# Memory.net
KiCad netlist of a schematic drawn in Altium Designer
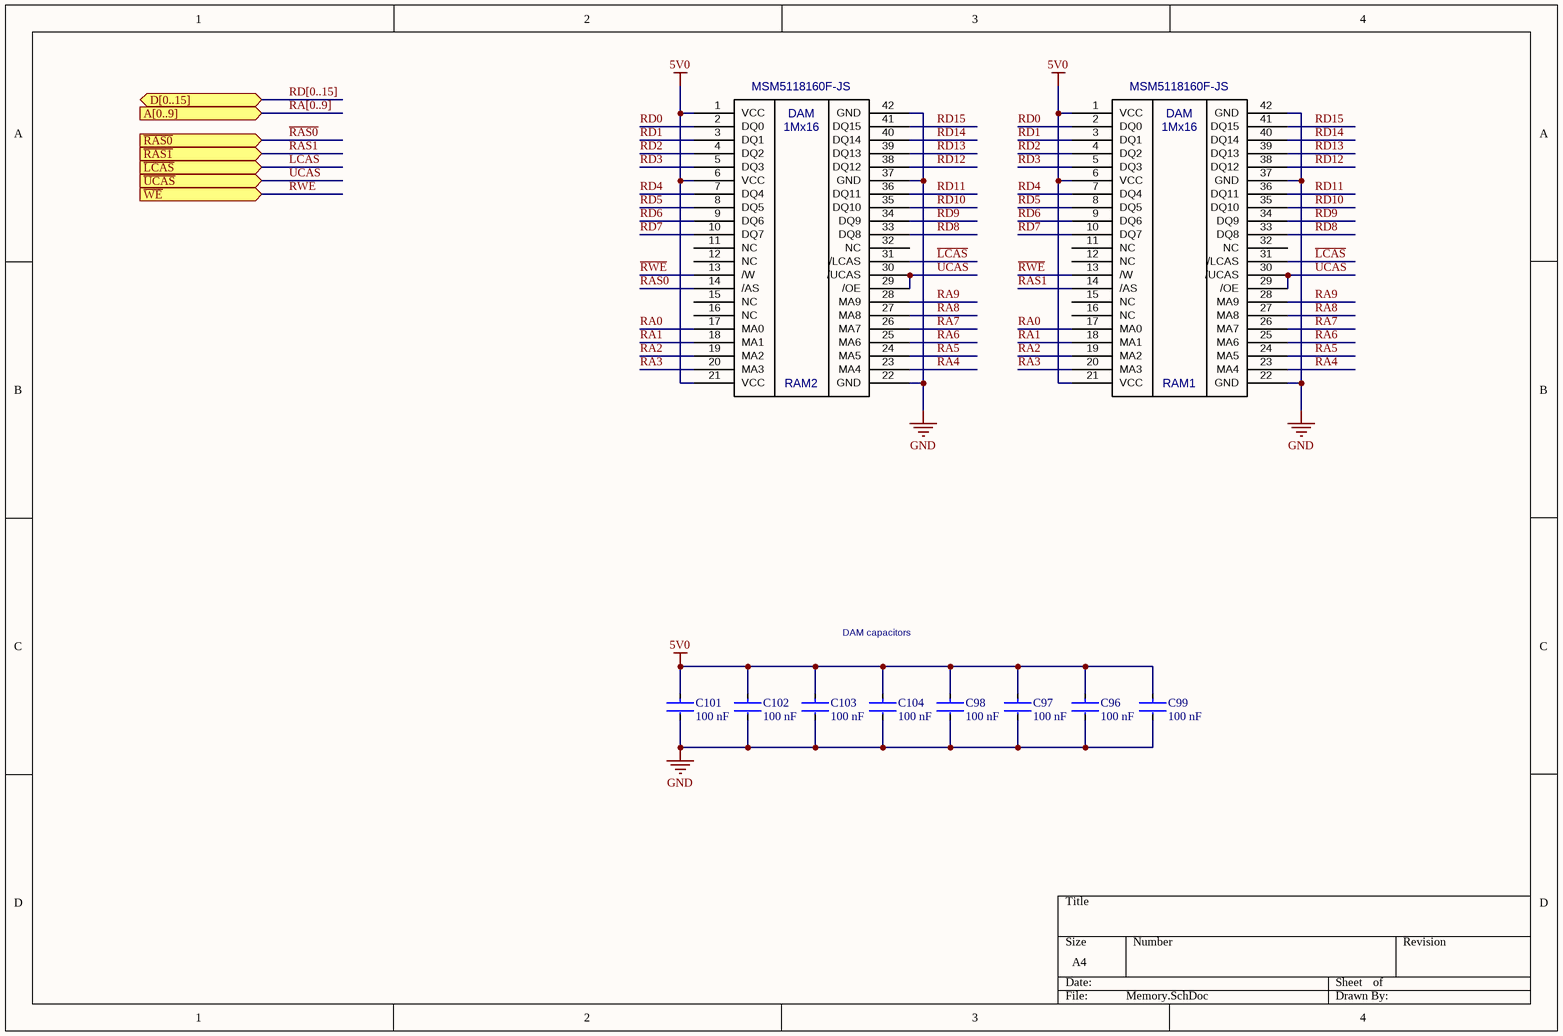
[diagram p0: Memory.SchDoc]

(export (version "E")
  (design (tool "Eeschema 10.0.6"))
  (components
    (comp (ref "C96")
      (value "CC0805KRX7R9BB104")
      (footprint "FP-CC0805-0_85-IPC_A")
      (description "CAP CER 0.1UF 50V X7R 0805")
      (fields (field (name "CAPACITANCE") "100 nF") (field (name "MANUFACTURER") "Yageo"))
      (libsource (lib "SchLib") (part "CMP-2100-03606-3"))
    )
    (comp (ref "C97")
      (value "CC0805KRX7R9BB104")
      (footprint "FP-CC0805-0_85-IPC_A")
      (description "CAP CER 0.1UF 50V X7R 0805")
      (fields (field (name "CAPACITANCE") "100 nF") (field (name "MANUFACTURER") "Yageo"))
      (libsource (lib "SchLib") (part "CMP-2100-03606-3"))
    )
    (comp (ref "C98")
      (value "CC0805KRX7R9BB104")
      (footprint "FP-CC0805-0_85-IPC_A")
      (description "CAP CER 0.1UF 50V X7R 0805")
      (fields (field (name "CAPACITANCE") "100 nF") (field (name "MANUFACTURER") "Yageo"))
      (libsource (lib "SchLib") (part "CMP-2100-03606-3"))
    )
    (comp (ref "C99")
      (value "CC0805KRX7R9BB104")
      (footprint "FP-CC0805-0_85-IPC_A")
      (description "CAP CER 0.1UF 50V X7R 0805")
      (fields (field (name "CAPACITANCE") "100 nF") (field (name "MANUFACTURER") "Yageo"))
      (libsource (lib "SchLib") (part "CMP-2100-03606-3"))
    )
    (comp (ref "C101")
      (value "CC0805KRX7R9BB104")
      (footprint "FP-CC0805-0_85-IPC_A")
      (description "CAP CER 0.1UF 50V X7R 0805")
      (fields (field (name "CAPACITANCE") "100 nF") (field (name "MANUFACTURER") "Yageo"))
      (libsource (lib "SchLib") (part "CMP-2100-03606-3"))
    )
    (comp (ref "C102")
      (value "CC0805KRX7R9BB104")
      (footprint "FP-CC0805-0_85-IPC_A")
      (description "CAP CER 0.1UF 50V X7R 0805")
      (fields (field (name "CAPACITANCE") "100 nF") (field (name "MANUFACTURER") "Yageo"))
      (libsource (lib "SchLib") (part "CMP-2100-03606-3"))
    )
    (comp (ref "C103")
      (value "CC0805KRX7R9BB104")
      (footprint "FP-CC0805-0_85-IPC_A")
      (description "CAP CER 0.1UF 50V X7R 0805")
      (fields (field (name "CAPACITANCE") "100 nF") (field (name "MANUFACTURER") "Yageo"))
      (libsource (lib "SchLib") (part "CMP-2100-03606-3"))
    )
    (comp (ref "C104")
      (value "CC0805KRX7R9BB104")
      (footprint "FP-CC0805-0_85-IPC_A")
      (description "CAP CER 0.1UF 50V X7R 0805")
      (fields (field (name "CAPACITANCE") "100 nF") (field (name "MANUFACTURER") "Yageo"))
      (libsource (lib "SchLib") (part "CMP-2100-03606-3"))
    )
    (comp (ref "RAM1")
      (value "MSM5118160F-JS")
      (footprint "SOJ42")
      (libsource (lib "SchLib") (part "MSM5118160F-JS"))
    )
    (comp (ref "RAM2")
      (value "MSM5118160F-JS")
      (footprint "SOJ42")
      (libsource (lib "SchLib") (part "MSM5118160F-JS"))
    )
  )
  (nets
    (net (code "1") (name "/RA0") (class "Default")
      (node (ref "RAM1") (pin "17") (pinfunction "MA0_17") (pintype "passive"))
      (node (ref "RAM2") (pin "17") (pinfunction "MA0_17") (pintype "passive"))
    )
    (net (code "2") (name "/RA1") (class "Default")
      (node (ref "RAM1") (pin "18") (pinfunction "MA1_18") (pintype "passive"))
      (node (ref "RAM2") (pin "18") (pinfunction "MA1_18") (pintype "passive"))
    )
    (net (code "3") (name "/RA2") (class "Default")
      (node (ref "RAM1") (pin "19") (pinfunction "MA2_19") (pintype "passive"))
      (node (ref "RAM2") (pin "19") (pinfunction "MA2_19") (pintype "passive"))
    )
    (net (code "4") (name "/RA3") (class "Default")
      (node (ref "RAM1") (pin "20") (pinfunction "MA3_20") (pintype "passive"))
      (node (ref "RAM2") (pin "20") (pinfunction "MA3_20") (pintype "passive"))
    )
    (net (code "5") (name "/RA4") (class "Default")
      (node (ref "RAM1") (pin "23") (pinfunction "MA4_23") (pintype "passive"))
      (node (ref "RAM2") (pin "23") (pinfunction "MA4_23") (pintype "passive"))
    )
    (net (code "6") (name "/RA5") (class "Default")
      (node (ref "RAM1") (pin "24") (pinfunction "MA5_24") (pintype "passive"))
      (node (ref "RAM2") (pin "24") (pinfunction "MA5_24") (pintype "passive"))
    )
    (net (code "7") (name "/RA6") (class "Default")
      (node (ref "RAM1") (pin "25") (pinfunction "MA6_25") (pintype "passive"))
      (node (ref "RAM2") (pin "25") (pinfunction "MA6_25") (pintype "passive"))
    )
    (net (code "8") (name "/RA7") (class "Default")
      (node (ref "RAM1") (pin "26") (pinfunction "MA7_26") (pintype "passive"))
      (node (ref "RAM2") (pin "26") (pinfunction "MA7_26") (pintype "passive"))
    )
    (net (code "9") (name "/RA8") (class "Default")
      (node (ref "RAM1") (pin "27") (pinfunction "MA8_27") (pintype "passive"))
      (node (ref "RAM2") (pin "27") (pinfunction "MA8_27") (pintype "passive"))
    )
    (net (code "10") (name "/RA9") (class "Default")
      (node (ref "RAM1") (pin "28") (pinfunction "MA9_28") (pintype "passive"))
      (node (ref "RAM2") (pin "28") (pinfunction "MA9_28") (pintype "passive"))
    )
    (net (code "12") (name "/RD0") (class "Default")
      (node (ref "RAM1") (pin "2") (pinfunction "DQ0_2") (pintype "passive"))
      (node (ref "RAM2") (pin "2") (pinfunction "DQ0_2") (pintype "passive"))
    )
    (net (code "13") (name "/RD1") (class "Default")
      (node (ref "RAM1") (pin "3") (pinfunction "DQ1_3") (pintype "passive"))
      (node (ref "RAM2") (pin "3") (pinfunction "DQ1_3") (pintype "passive"))
    )
    (net (code "14") (name "/RD2") (class "Default")
      (node (ref "RAM1") (pin "4") (pinfunction "DQ2_4") (pintype "passive"))
      (node (ref "RAM2") (pin "4") (pinfunction "DQ2_4") (pintype "passive"))
    )
    (net (code "15") (name "/RD3") (class "Default")
      (node (ref "RAM1") (pin "5") (pinfunction "DQ3_5") (pintype "passive"))
      (node (ref "RAM2") (pin "5") (pinfunction "DQ3_5") (pintype "passive"))
    )
    (net (code "16") (name "/RD4") (class "Default")
      (node (ref "RAM1") (pin "7") (pinfunction "DQ4_7") (pintype "passive"))
      (node (ref "RAM2") (pin "7") (pinfunction "DQ4_7") (pintype "passive"))
    )
    (net (code "17") (name "/RD5") (class "Default")
      (node (ref "RAM1") (pin "8") (pinfunction "DQ5_8") (pintype "passive"))
      (node (ref "RAM2") (pin "8") (pinfunction "DQ5_8") (pintype "passive"))
    )
    (net (code "18") (name "/RD6") (class "Default")
      (node (ref "RAM1") (pin "9") (pinfunction "DQ6_9") (pintype "passive"))
      (node (ref "RAM2") (pin "9") (pinfunction "DQ6_9") (pintype "passive"))
    )
    (net (code "19") (name "/RD7") (class "Default")
      (node (ref "RAM1") (pin "10") (pinfunction "DQ7_10") (pintype "passive"))
      (node (ref "RAM2") (pin "10") (pinfunction "DQ7_10") (pintype "passive"))
    )
    (net (code "20") (name "/RD8") (class "Default")
      (node (ref "RAM1") (pin "33") (pinfunction "DQ8_33") (pintype "passive"))
      (node (ref "RAM2") (pin "33") (pinfunction "DQ8_33") (pintype "passive"))
    )
    (net (code "21") (name "/RD9") (class "Default")
      (node (ref "RAM1") (pin "34") (pinfunction "DQ9_34") (pintype "passive"))
      (node (ref "RAM2") (pin "34") (pinfunction "DQ9_34") (pintype "passive"))
    )
    (net (code "22") (name "/RD10") (class "Default")
      (node (ref "RAM1") (pin "35") (pinfunction "DQ10_35") (pintype "passive"))
      (node (ref "RAM2") (pin "35") (pinfunction "DQ10_35") (pintype "passive"))
    )
    (net (code "23") (name "/RD11") (class "Default")
      (node (ref "RAM1") (pin "36") (pinfunction "DQ11_36") (pintype "passive"))
      (node (ref "RAM2") (pin "36") (pinfunction "DQ11_36") (pintype "passive"))
    )
    (net (code "24") (name "/RD12") (class "Default")
      (node (ref "RAM1") (pin "38") (pinfunction "DQ12_38") (pintype "passive"))
      (node (ref "RAM2") (pin "38") (pinfunction "DQ12_38") (pintype "passive"))
    )
    (net (code "25") (name "/RD13") (class "Default")
      (node (ref "RAM1") (pin "39") (pinfunction "DQ13_39") (pintype "passive"))
      (node (ref "RAM2") (pin "39") (pinfunction "DQ13_39") (pintype "passive"))
    )
    (net (code "26") (name "/RD14") (class "Default")
      (node (ref "RAM1") (pin "40") (pinfunction "DQ14_40") (pintype "passive"))
      (node (ref "RAM2") (pin "40") (pinfunction "DQ14_40") (pintype "passive"))
    )
    (net (code "27") (name "/RD15") (class "Default")
      (node (ref "RAM1") (pin "41") (pinfunction "DQ15_41") (pintype "passive"))
      (node (ref "RAM2") (pin "41") (pinfunction "DQ15_41") (pintype "passive"))
    )
    (net (code "29") (name "/~{LCAS}") (class "Default")
      (node (ref "RAM1") (pin "31") (pinfunction "/LCAS_31") (pintype "passive"))
      (node (ref "RAM2") (pin "31") (pinfunction "/LCAS_31") (pintype "passive"))
    )
    (net (code "30") (name "/~{RAS0}") (class "Default")
      (node (ref "RAM2") (pin "14") (pinfunction "/AS_14") (pintype "passive"))
    )
    (net (code "31") (name "/~{RAS1}") (class "Default")
      (node (ref "RAM1") (pin "14") (pinfunction "/AS_14") (pintype "passive"))
    )
    (net (code "32") (name "/~{RWE}") (class "Default")
      (node (ref "RAM1") (pin "13") (pinfunction "/W_13") (pintype "passive"))
      (node (ref "RAM2") (pin "13") (pinfunction "/W_13") (pintype "passive"))
    )
    (net (code "33") (name "/~{UCAS}") (class "Default")
      (node (ref "RAM1") (pin "29") (pinfunction "/OE_29") (pintype "passive"))
      (node (ref "RAM1") (pin "30") (pinfunction "/UCAS_30") (pintype "passive"))
      (node (ref "RAM2") (pin "29") (pinfunction "/OE_29") (pintype "passive"))
      (node (ref "RAM2") (pin "30") (pinfunction "/UCAS_30") (pintype "passive"))
    )
    (net (code "34") (name "5V0") (class "Default")
      (node (ref "C101") (pin "1") (pinfunction "1_1") (pintype "passive"))
      (node (ref "C102") (pin "1") (pinfunction "1_1") (pintype "passive"))
      (node (ref "C103") (pin "1") (pinfunction "1_1") (pintype "passive"))
      (node (ref "C104") (pin "1") (pinfunction "1_1") (pintype "passive"))
      (node (ref "C96") (pin "1") (pinfunction "1_1") (pintype "passive"))
      (node (ref "C97") (pin "1") (pinfunction "1_1") (pintype "passive"))
      (node (ref "C98") (pin "1") (pinfunction "1_1") (pintype "passive"))
      (node (ref "C99") (pin "1") (pinfunction "1_1") (pintype "passive"))
      (node (ref "RAM1") (pin "1") (pinfunction "VCC_1") (pintype "passive"))
      (node (ref "RAM1") (pin "21") (pinfunction "VCC_21") (pintype "passive"))
      (node (ref "RAM1") (pin "6") (pinfunction "VCC_6") (pintype "passive"))
      (node (ref "RAM2") (pin "1") (pinfunction "VCC_1") (pintype "passive"))
      (node (ref "RAM2") (pin "21") (pinfunction "VCC_21") (pintype "passive"))
      (node (ref "RAM2") (pin "6") (pinfunction "VCC_6") (pintype "passive"))
    )
    (net (code "35") (name "GND") (class "Default")
      (node (ref "C101") (pin "2") (pinfunction "2_2") (pintype "passive"))
      (node (ref "C102") (pin "2") (pinfunction "2_2") (pintype "passive"))
      (node (ref "C103") (pin "2") (pinfunction "2_2") (pintype "passive"))
      (node (ref "C104") (pin "2") (pinfunction "2_2") (pintype "passive"))
      (node (ref "C96") (pin "2") (pinfunction "2_2") (pintype "passive"))
      (node (ref "C97") (pin "2") (pinfunction "2_2") (pintype "passive"))
      (node (ref "C98") (pin "2") (pinfunction "2_2") (pintype "passive"))
      (node (ref "C99") (pin "2") (pinfunction "2_2") (pintype "passive"))
      (node (ref "RAM1") (pin "22") (pinfunction "GND_22") (pintype "passive"))
      (node (ref "RAM1") (pin "37") (pinfunction "GND_37") (pintype "passive"))
      (node (ref "RAM1") (pin "42") (pinfunction "GND_42") (pintype "passive"))
      (node (ref "RAM2") (pin "22") (pinfunction "GND_22") (pintype "passive"))
      (node (ref "RAM2") (pin "37") (pinfunction "GND_37") (pintype "passive"))
      (node (ref "RAM2") (pin "42") (pinfunction "GND_42") (pintype "passive"))
    )
    (net (code "36") (name "unconnected-(RAM1-NC-Pad11)") (class "Default")
      (node (ref "RAM1") (pin "11") (pinfunction "NC_11") (pintype "passive"))
    )
    (net (code "37") (name "unconnected-(RAM1-NC-Pad12)") (class "Default")
      (node (ref "RAM1") (pin "12") (pinfunction "NC_12") (pintype "passive"))
    )
    (net (code "38") (name "unconnected-(RAM1-NC-Pad15)") (class "Default")
      (node (ref "RAM1") (pin "15") (pinfunction "NC_15") (pintype "passive"))
    )
    (net (code "39") (name "unconnected-(RAM1-NC-Pad16)") (class "Default")
      (node (ref "RAM1") (pin "16") (pinfunction "NC_16") (pintype "passive"))
    )
    (net (code "40") (name "unconnected-(RAM1-NC-Pad32)") (class "Default")
      (node (ref "RAM1") (pin "32") (pinfunction "NC_32") (pintype "passive"))
    )
    (net (code "41") (name "unconnected-(RAM2-NC-Pad11)") (class "Default")
      (node (ref "RAM2") (pin "11") (pinfunction "NC_11") (pintype "passive"))
    )
    (net (code "42") (name "unconnected-(RAM2-NC-Pad12)") (class "Default")
      (node (ref "RAM2") (pin "12") (pinfunction "NC_12") (pintype "passive"))
    )
    (net (code "43") (name "unconnected-(RAM2-NC-Pad15)") (class "Default")
      (node (ref "RAM2") (pin "15") (pinfunction "NC_15") (pintype "passive"))
    )
    (net (code "44") (name "unconnected-(RAM2-NC-Pad16)") (class "Default")
      (node (ref "RAM2") (pin "16") (pinfunction "NC_16") (pintype "passive"))
    )
    (net (code "45") (name "unconnected-(RAM2-NC-Pad32)") (class "Default")
      (node (ref "RAM2") (pin "32") (pinfunction "NC_32") (pintype "passive"))
    )
  )
)
